# homecomputer-6502.net
KiCad netlist of a schematic drawn in EAGLE
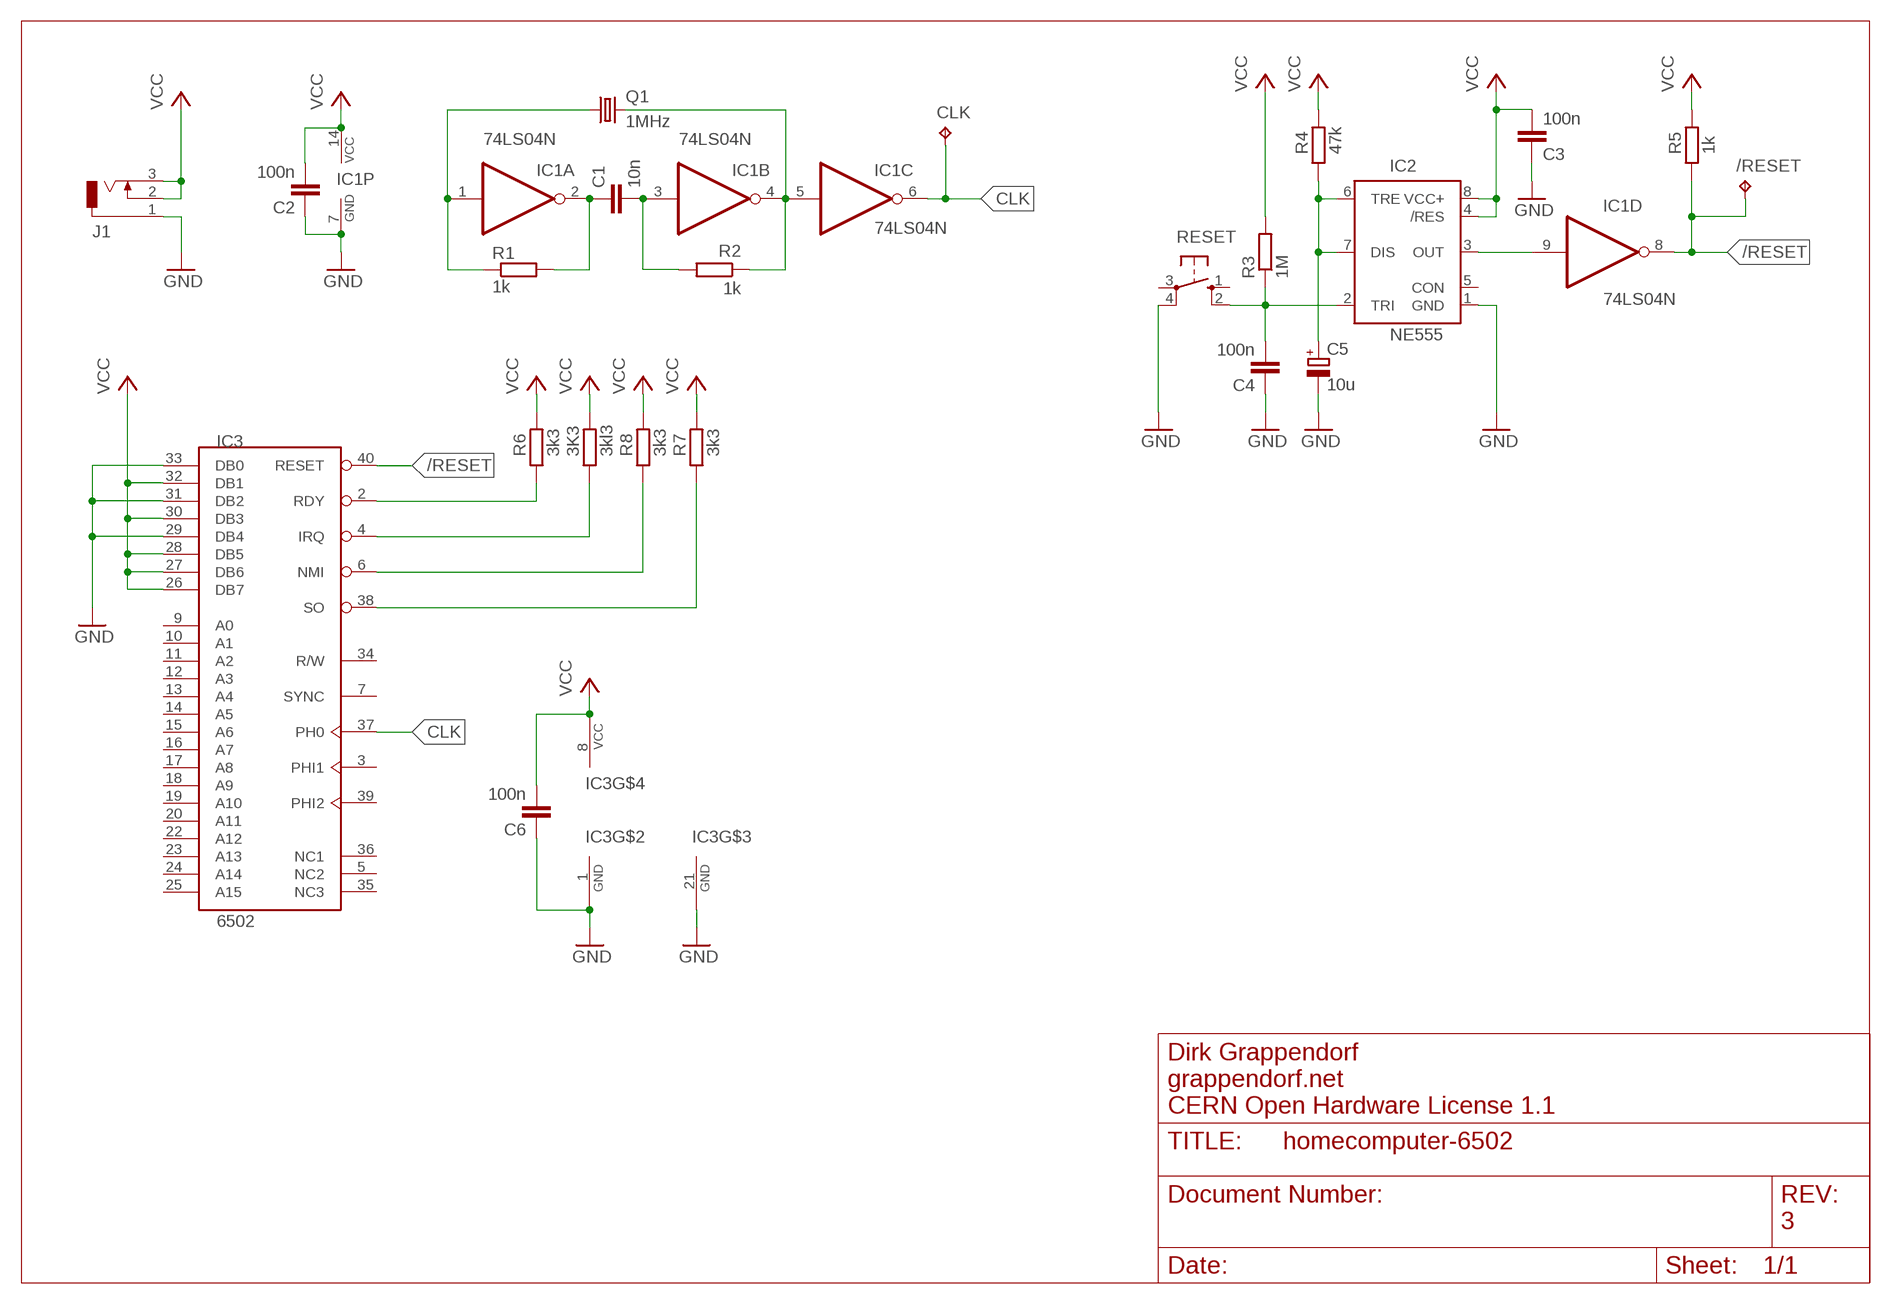
[diagram p0: schematic, sheet 1]

(export (version "E")
  (design (tool "Eeschema 10.0.6"))
  (components
    (comp (ref "/RESET")
      (value "TPPAD1-13")
      (footprint "eagle-import:P1-13")
      (libsource (lib "eagle-import") (part "TPPAD1-13"))
    )
    (comp (ref "3K3")
      (value "3kl3")
      (footprint "eagle-import:0204_5")
      (libsource (lib "eagle-import") (part "R-EU_0204/5"))
    )
    (comp (ref "C1")
      (value "10n")
      (footprint "eagle-import:C025-024X044")
      (libsource (lib "eagle-import") (part "C-EU025-024X044"))
    )
    (comp (ref "C2")
      (value "100n")
      (footprint "eagle-import:C025-024X044")
      (libsource (lib "eagle-import") (part "C-EU025-024X044"))
    )
    (comp (ref "C3")
      (value "100n")
      (footprint "eagle-import:C025-024X044")
      (libsource (lib "eagle-import") (part "C-EU025-024X044"))
    )
    (comp (ref "C4")
      (value "100n")
      (footprint "eagle-import:C025-024X044")
      (libsource (lib "eagle-import") (part "C-EU025-024X044"))
    )
    (comp (ref "C5")
      (value "10u")
      (footprint "eagle-import:E2,5-6E")
      (libsource (lib "eagle-import") (part "CPOL-EUE2,5-6E"))
    )
    (comp (ref "C6")
      (value "100n")
      (footprint "eagle-import:C025-024X044")
      (libsource (lib "eagle-import") (part "C-EU025-024X044"))
    )
    (comp (ref "CLK")
      (value "TPPAD1-13")
      (footprint "eagle-import:P1-13")
      (libsource (lib "eagle-import") (part "TPPAD1-13"))
    )
    (comp (ref "IC1")
      (value "74LS04N")
      (footprint "eagle-import:DIL14")
      (libsource (lib "eagle-import") (part "7404NLS"))
    )
    (comp (ref "IC2")
      (value "NE555")
      (footprint "eagle-import:DIL-08")
      (fields (field (name "MF") "Arrow Electronics") (field (name "MPN") "NE555N"))
      (libsource (lib "eagle-import") (part "NE555"))
    )
    (comp (ref "IC3")
      (value "6502")
      (footprint "eagle-import:DIP40")
      (libsource (lib "eagle-import") (part "6502"))
    )
    (comp (ref "J1")
      (value "DCJ0303")
      (footprint "eagle-import:DCJ0303")
      (libsource (lib "eagle-import") (part "DCJ0303"))
    )
    (comp (ref "Q1")
      (value "1MHz")
      (footprint "eagle-import:HC49U-V")
      (libsource (lib "eagle-import") (part "CRYSTALHC49U-V"))
    )
    (comp (ref "R1")
      (value "1k")
      (footprint "eagle-import:0204_5")
      (libsource (lib "eagle-import") (part "R-EU_0204/5"))
    )
    (comp (ref "R2")
      (value "1k")
      (footprint "eagle-import:0204_5")
      (libsource (lib "eagle-import") (part "R-EU_0204/5"))
    )
    (comp (ref "R3")
      (value "1M")
      (footprint "eagle-import:0204_5")
      (libsource (lib "eagle-import") (part "R-EU_0204/5"))
    )
    (comp (ref "R4")
      (value "47k")
      (footprint "eagle-import:0204_5")
      (libsource (lib "eagle-import") (part "R-EU_0204/5"))
    )
    (comp (ref "R5")
      (value "1k")
      (footprint "eagle-import:0204_5")
      (libsource (lib "eagle-import") (part "R-EU_0204/5"))
    )
    (comp (ref "R6")
      (value "3k3")
      (footprint "eagle-import:0204_5")
      (libsource (lib "eagle-import") (part "R-EU_0204/5"))
    )
    (comp (ref "R7")
      (value "3k3")
      (footprint "eagle-import:0204_5")
      (libsource (lib "eagle-import") (part "R-EU_0204/5"))
    )
    (comp (ref "R8")
      (value "3k3")
      (footprint "eagle-import:0204_5")
      (libsource (lib "eagle-import") (part "R-EU_0204/5"))
    )
    (comp (ref "RESET")
      (value "10-XX")
      (footprint "eagle-import:B3F-10XX")
      (fields (field (name "MPN") "B3F-1000"))
      (libsource (lib "eagle-import") (part "10-XX"))
    )
  )
  (nets
    (net (code "1") (name "CLK") (class "Default")
      (node (ref "CLK") (pin "TP") (pinfunction "TP_TP") (pintype "input"))
      (node (ref "IC1") (pin "6") (pinfunction "O_6") (pintype "output"))
      (node (ref "IC3") (pin "37") (pinfunction "PH0_37") (pintype "input"))
    )
    (net (code "2") (name "GND") (class "Default")
      (node (ref "C2") (pin "1") (pinfunction "1_1") (pintype "passive"))
      (node (ref "C3") (pin "1") (pinfunction "1_1") (pintype "passive"))
      (node (ref "C4") (pin "1") (pinfunction "1_1") (pintype "passive"))
      (node (ref "C5") (pin "-") (pinfunction "-_-") (pintype "passive"))
      (node (ref "C6") (pin "1") (pinfunction "1_1") (pintype "passive"))
      (node (ref "IC1") (pin "7") (pinfunction "GND_7") (pintype "power_in"))
      (node (ref "IC2") (pin "1") (pinfunction "GND_1") (pintype "power_in"))
      (node (ref "IC3") (pin "1") (pinfunction "GND_1") (pintype "power_in"))
      (node (ref "IC3") (pin "21") (pinfunction "GND_21") (pintype "power_in"))
      (node (ref "IC3") (pin "29") (pinfunction "DB4_29") (pintype "bidirectional"))
      (node (ref "IC3") (pin "31") (pinfunction "DB2_31") (pintype "bidirectional"))
      (node (ref "IC3") (pin "33") (pinfunction "DB0_33") (pintype "bidirectional"))
      (node (ref "J1") (pin "1") (pinfunction "1_1") (pintype "passive"))
      (node (ref "RESET") (pin "4") (pinfunction "P1_4") (pintype "passive"))
    )
    (net (code "3") (name "Net-(IC1A-I)") (class "Default")
      (node (ref "IC1") (pin "1") (pinfunction "I_1") (pintype "input"))
      (node (ref "Q1") (pin "1") (pinfunction "1_1") (pintype "passive"))
      (node (ref "R1") (pin "1") (pinfunction "1_1") (pintype "passive"))
    )
    (net (code "4") (name "Net-(IC1A-O)") (class "Default")
      (node (ref "C1") (pin "1") (pinfunction "1_1") (pintype "passive"))
      (node (ref "IC1") (pin "2") (pinfunction "O_2") (pintype "output"))
      (node (ref "R1") (pin "2") (pinfunction "2_2") (pintype "passive"))
    )
    (net (code "5") (name "Net-(IC1B-I)") (class "Default")
      (node (ref "C1") (pin "2") (pinfunction "2_2") (pintype "passive"))
      (node (ref "IC1") (pin "3") (pinfunction "I_3") (pintype "input"))
      (node (ref "R2") (pin "2") (pinfunction "2_2") (pintype "passive"))
    )
    (net (code "6") (name "Net-(IC1B-O)") (class "Default")
      (node (ref "IC1") (pin "4") (pinfunction "O_4") (pintype "output"))
      (node (ref "IC1") (pin "5") (pinfunction "I_5") (pintype "input"))
      (node (ref "Q1") (pin "2") (pinfunction "2_2") (pintype "passive"))
      (node (ref "R2") (pin "1") (pinfunction "1_1") (pintype "passive"))
    )
    (net (code "7") (name "Net-(IC1D-I)") (class "Default")
      (node (ref "IC1") (pin "9") (pinfunction "I_9") (pintype "input"))
      (node (ref "IC2") (pin "3") (pinfunction "OUT_3") (pintype "output"))
    )
    (net (code "8") (name "Net-(IC2-DIS)") (class "Default")
      (node (ref "C5") (pin "+") (pinfunction "+_+") (pintype "passive"))
      (node (ref "IC2") (pin "6") (pinfunction "TRE_6") (pintype "input"))
      (node (ref "IC2") (pin "7") (pinfunction "DIS_7") (pintype "input"))
      (node (ref "R4") (pin "1") (pinfunction "1_1") (pintype "passive"))
    )
    (net (code "9") (name "Net-(IC2-TRI)") (class "Default")
      (node (ref "C4") (pin "2") (pinfunction "2_2") (pintype "passive"))
      (node (ref "IC2") (pin "2") (pinfunction "TRI_2") (pintype "input"))
      (node (ref "R3") (pin "1") (pinfunction "1_1") (pintype "passive"))
      (node (ref "RESET") (pin "2") (pinfunction "S1_2") (pintype "passive"))
    )
    (net (code "10") (name "Net-(IC3A-IRQ)") (class "Default")
      (node (ref "3K3") (pin "1") (pinfunction "1_1") (pintype "passive"))
      (node (ref "IC3") (pin "4") (pinfunction "IRQ_4") (pintype "input"))
    )
    (net (code "11") (name "Net-(IC3A-NMI)") (class "Default")
      (node (ref "IC3") (pin "6") (pinfunction "NMI_6") (pintype "input"))
      (node (ref "R8") (pin "1") (pinfunction "1_1") (pintype "passive"))
    )
    (net (code "12") (name "Net-(IC3A-RDY)") (class "Default")
      (node (ref "IC3") (pin "2") (pinfunction "RDY_2") (pintype "input"))
      (node (ref "R6") (pin "1") (pinfunction "1_1") (pintype "passive"))
    )
    (net (code "13") (name "Net-(IC3A-SO)") (class "Default")
      (node (ref "IC3") (pin "38") (pinfunction "SO_38") (pintype "input"))
      (node (ref "R7") (pin "1") (pinfunction "1_1") (pintype "passive"))
    )
    (net (code "14") (name "VCC") (class "Default")
      (node (ref "3K3") (pin "2") (pinfunction "2_2") (pintype "passive"))
      (node (ref "C2") (pin "2") (pinfunction "2_2") (pintype "passive"))
      (node (ref "C3") (pin "2") (pinfunction "2_2") (pintype "passive"))
      (node (ref "C6") (pin "2") (pinfunction "2_2") (pintype "passive"))
      (node (ref "IC1") (pin "14") (pinfunction "VCC_14") (pintype "power_in"))
      (node (ref "IC2") (pin "4") (pinfunction "/RES_4") (pintype "input"))
      (node (ref "IC2") (pin "8") (pinfunction "VCC+_8") (pintype "power_in"))
      (node (ref "IC3") (pin "26") (pinfunction "DB7_26") (pintype "bidirectional"))
      (node (ref "IC3") (pin "27") (pinfunction "DB6_27") (pintype "bidirectional"))
      (node (ref "IC3") (pin "28") (pinfunction "DB5_28") (pintype "bidirectional"))
      (node (ref "IC3") (pin "30") (pinfunction "DB3_30") (pintype "bidirectional"))
      (node (ref "IC3") (pin "32") (pinfunction "DB1_32") (pintype "bidirectional"))
      (node (ref "IC3") (pin "8") (pinfunction "VCC_8") (pintype "power_in"))
      (node (ref "J1") (pin "2") (pinfunction "2_2") (pintype "passive"))
      (node (ref "J1") (pin "3") (pinfunction "3_3") (pintype "passive"))
      (node (ref "R3") (pin "2") (pinfunction "2_2") (pintype "passive"))
      (node (ref "R4") (pin "2") (pinfunction "2_2") (pintype "passive"))
      (node (ref "R5") (pin "2") (pinfunction "2_2") (pintype "passive"))
      (node (ref "R6") (pin "2") (pinfunction "2_2") (pintype "passive"))
      (node (ref "R7") (pin "2") (pinfunction "2_2") (pintype "passive"))
      (node (ref "R8") (pin "2") (pinfunction "2_2") (pintype "passive"))
    )
    (net (code "15") (name "unconnected-(IC2-CON-Pad5)") (class "Default")
      (node (ref "IC2") (pin "5") (pinfunction "CON_5") (pintype "input"))
    )
    (net (code "16") (name "unconnected-(IC3A-A0-Pad9)") (class "Default")
      (node (ref "IC3") (pin "9") (pinfunction "A0_9") (pintype "output"))
    )
    (net (code "17") (name "unconnected-(IC3A-A1-Pad10)") (class "Default")
      (node (ref "IC3") (pin "10") (pinfunction "A1_10") (pintype "output"))
    )
    (net (code "18") (name "unconnected-(IC3A-A2-Pad11)") (class "Default")
      (node (ref "IC3") (pin "11") (pinfunction "A2_11") (pintype "output"))
    )
    (net (code "19") (name "unconnected-(IC3A-A3-Pad12)") (class "Default")
      (node (ref "IC3") (pin "12") (pinfunction "A3_12") (pintype "output"))
    )
    (net (code "20") (name "unconnected-(IC3A-A4-Pad13)") (class "Default")
      (node (ref "IC3") (pin "13") (pinfunction "A4_13") (pintype "output"))
    )
    (net (code "21") (name "unconnected-(IC3A-A5-Pad14)") (class "Default")
      (node (ref "IC3") (pin "14") (pinfunction "A5_14") (pintype "output"))
    )
    (net (code "22") (name "unconnected-(IC3A-A6-Pad15)") (class "Default")
      (node (ref "IC3") (pin "15") (pinfunction "A6_15") (pintype "output"))
    )
    (net (code "23") (name "unconnected-(IC3A-A7-Pad16)") (class "Default")
      (node (ref "IC3") (pin "16") (pinfunction "A7_16") (pintype "output"))
    )
    (net (code "24") (name "unconnected-(IC3A-A8-Pad17)") (class "Default")
      (node (ref "IC3") (pin "17") (pinfunction "A8_17") (pintype "output"))
    )
    (net (code "25") (name "unconnected-(IC3A-A9-Pad18)") (class "Default")
      (node (ref "IC3") (pin "18") (pinfunction "A9_18") (pintype "output"))
    )
    (net (code "26") (name "unconnected-(IC3A-A10-Pad19)") (class "Default")
      (node (ref "IC3") (pin "19") (pinfunction "A10_19") (pintype "output"))
    )
    (net (code "27") (name "unconnected-(IC3A-A11-Pad20)") (class "Default")
      (node (ref "IC3") (pin "20") (pinfunction "A11_20") (pintype "output"))
    )
    (net (code "28") (name "unconnected-(IC3A-A12-Pad22)") (class "Default")
      (node (ref "IC3") (pin "22") (pinfunction "A12_22") (pintype "output"))
    )
    (net (code "29") (name "unconnected-(IC3A-A13-Pad23)") (class "Default")
      (node (ref "IC3") (pin "23") (pinfunction "A13_23") (pintype "output"))
    )
    (net (code "30") (name "unconnected-(IC3A-A14-Pad24)") (class "Default")
      (node (ref "IC3") (pin "24") (pinfunction "A14_24") (pintype "output"))
    )
    (net (code "31") (name "unconnected-(IC3A-A15-Pad25)") (class "Default")
      (node (ref "IC3") (pin "25") (pinfunction "A15_25") (pintype "output"))
    )
    (net (code "32") (name "unconnected-(IC3A-NC1-Pad36)") (class "Default")
      (node (ref "IC3") (pin "36") (pinfunction "NC1_36") (pintype "passive"))
    )
    (net (code "33") (name "unconnected-(IC3A-NC2-Pad5)") (class "Default")
      (node (ref "IC3") (pin "5") (pinfunction "NC2_5") (pintype "passive"))
    )
    (net (code "34") (name "unconnected-(IC3A-NC3-Pad35)") (class "Default")
      (node (ref "IC3") (pin "35") (pinfunction "NC3_35") (pintype "passive"))
    )
    (net (code "35") (name "unconnected-(IC3A-PHI1-Pad3)") (class "Default")
      (node (ref "IC3") (pin "3") (pinfunction "PHI1_3") (pintype "output"))
    )
    (net (code "36") (name "unconnected-(IC3A-PHI2-Pad39)") (class "Default")
      (node (ref "IC3") (pin "39") (pinfunction "PHI2_39") (pintype "output"))
    )
    (net (code "37") (name "unconnected-(IC3A-R{slash}W-Pad34)") (class "Default")
      (node (ref "IC3") (pin "34") (pinfunction "R/W_34") (pintype "output"))
    )
    (net (code "38") (name "unconnected-(IC3A-SYNC-Pad7)") (class "Default")
      (node (ref "IC3") (pin "7") (pinfunction "SYNC_7") (pintype "output"))
    )
    (net (code "39") (name "unconnected-(RESET-P-Pad3)") (class "Default")
      (node (ref "RESET") (pin "3") (pinfunction "P_3") (pintype "passive"))
    )
    (net (code "40") (name "unconnected-(RESET-S-Pad1)") (class "Default")
      (node (ref "RESET") (pin "1") (pinfunction "S_1") (pintype "passive"))
    )
    (net (code "41") (name "{slash}RESET") (class "Default")
      (node (ref "/RESET") (pin "TP") (pinfunction "TP_TP") (pintype "input"))
      (node (ref "IC1") (pin "8") (pinfunction "O_8") (pintype "output"))
      (node (ref "IC3") (pin "40") (pinfunction "RESET_40") (pintype "input"))
      (node (ref "R5") (pin "1") (pinfunction "1_1") (pintype "passive"))
    )
  )
)
